# machxo2-breakout-v2.net
KiCad netlist of a schematic drawn in EAGLE
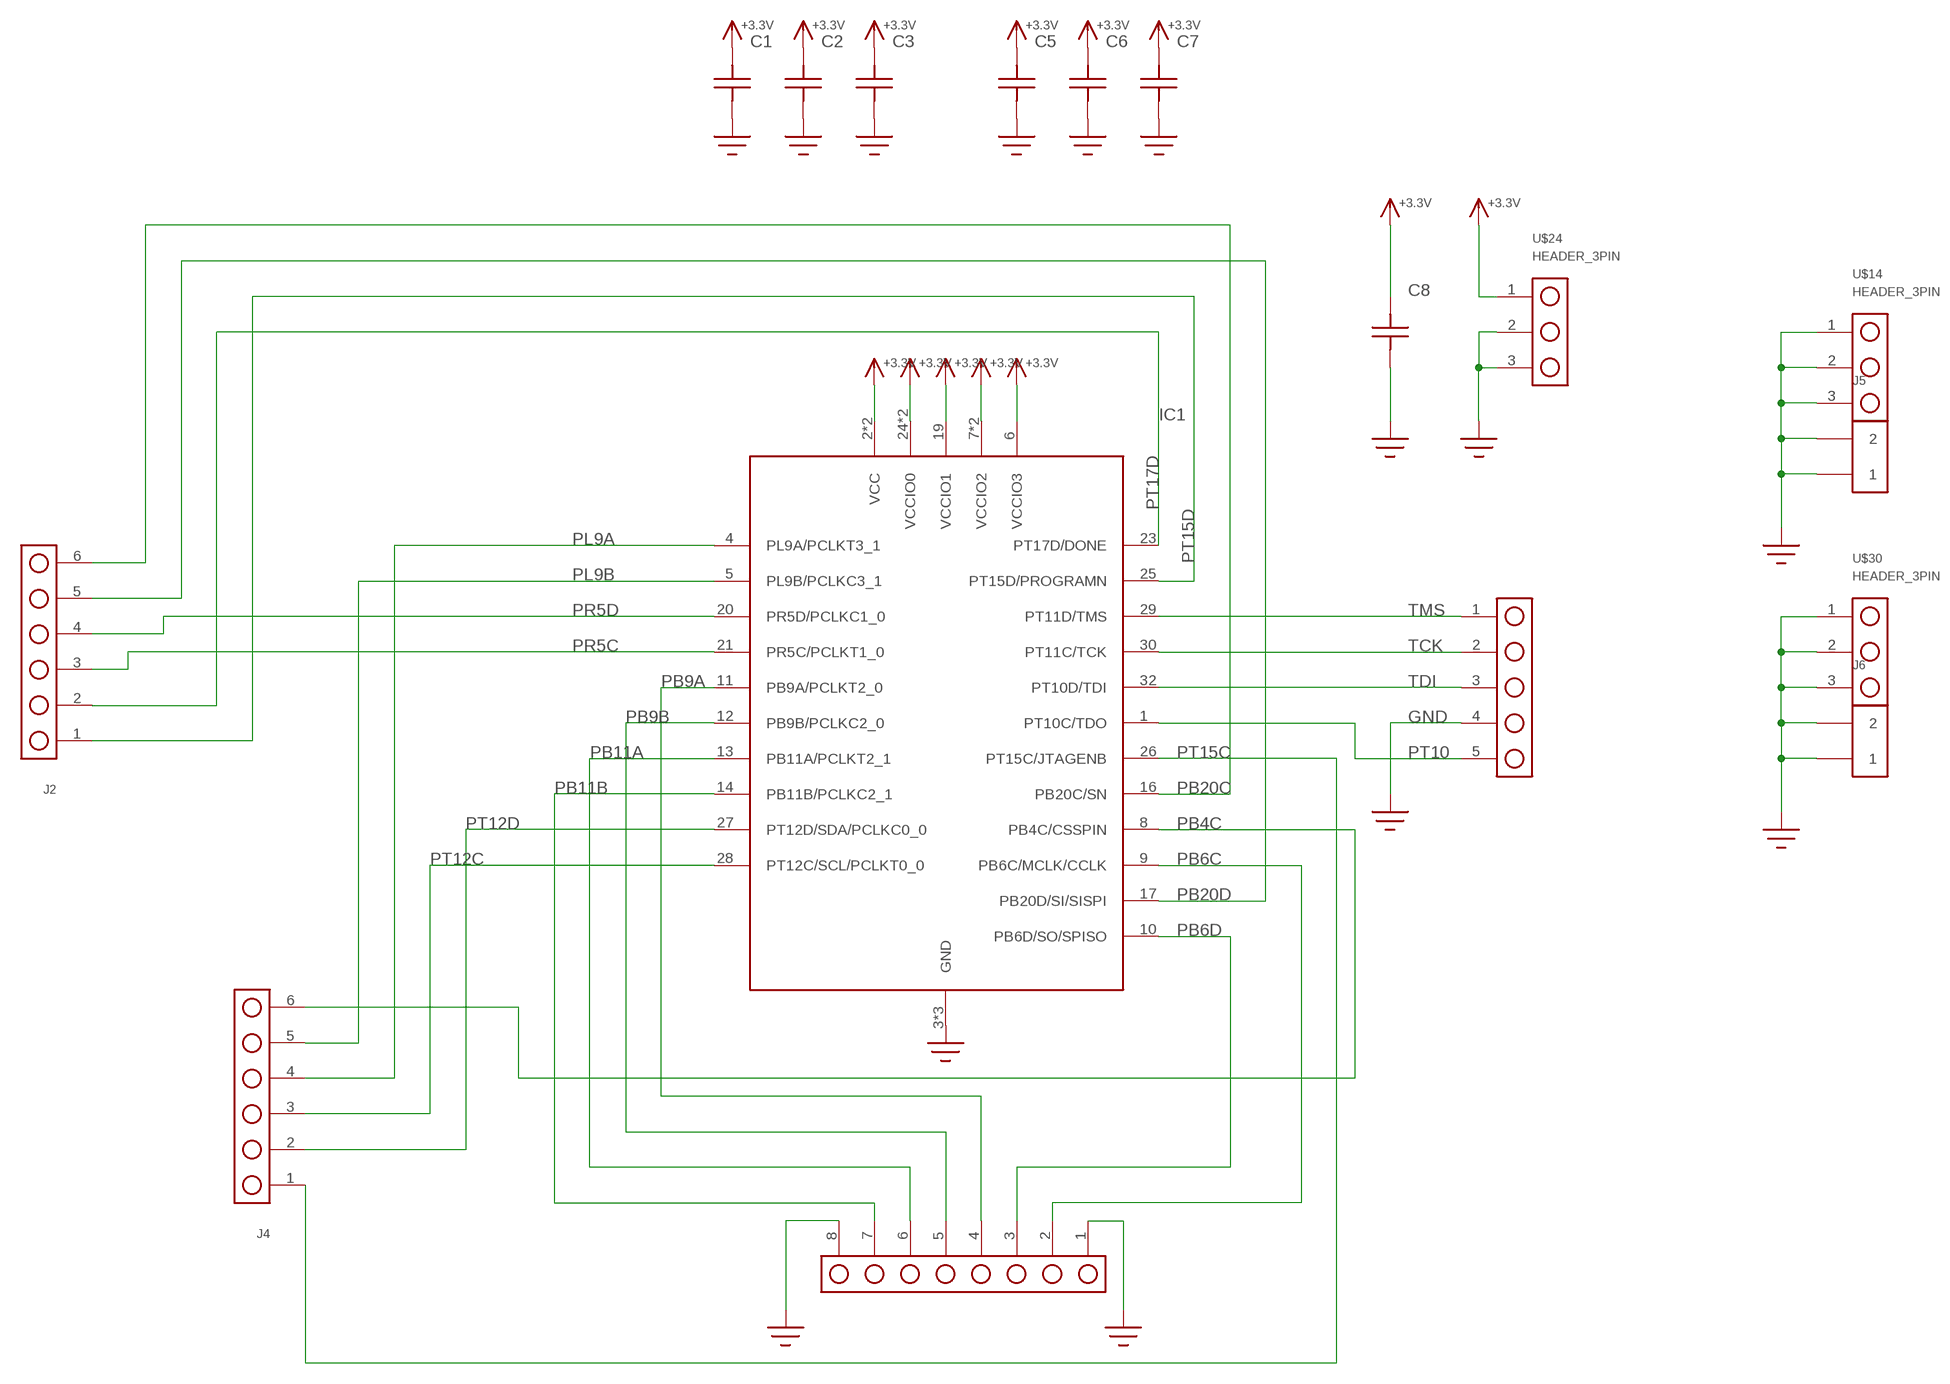
[diagram p0: schematic, sheet 1]

(export (version "E")
  (design (tool "Eeschema 10.0.6"))
  (components
    (comp (ref "C1") (value "C") (footprint "eagle-import:C0402") (libsource (lib "eagle-import") (part "C")))
    (comp (ref "C2") (value "C") (footprint "eagle-import:C0402") (libsource (lib "eagle-import") (part "C")))
    (comp (ref "C3") (value "C") (footprint "eagle-import:C0402") (libsource (lib "eagle-import") (part "C")))
    (comp (ref "C5") (value "C") (footprint "eagle-import:C0402") (libsource (lib "eagle-import") (part "C")))
    (comp (ref "C6") (value "C") (footprint "eagle-import:C0402") (libsource (lib "eagle-import") (part "C")))
    (comp (ref "C7") (value "C") (footprint "eagle-import:C0402") (libsource (lib "eagle-import") (part "C")))
    (comp (ref "C8")
      (value "C1206")
      (footprint "eagle-import:1206")
      (libsource (lib "eagle-import") (part "C1206"))
    )
    (comp (ref "IC1")
      (value "MACHXO2_1200EXTENDED")
      (footprint "eagle-import:QFN32_5X5-EXTENDED")
      (libsource (lib "eagle-import") (part "MACHXO2_1200EXTENDED"))
    )
    (comp (ref "J1")
      (value "HEADER_5PIN")
      (footprint "eagle-import:HEADER_5PIN")
      (libsource (lib "eagle-import") (part "HEADER_5PIN"))
    )
    (comp (ref "J2")
      (value "HEADER_6PIN")
      (footprint "eagle-import:HEADER_6PIN")
      (libsource (lib "eagle-import") (part "HEADER_6PIN"))
    )
    (comp (ref "J3")
      (value "HEADER_8PIN")
      (footprint "eagle-import:HEADER_8_PIN")
      (libsource (lib "eagle-import") (part "HEADER_8PIN"))
    )
    (comp (ref "J4")
      (value "HEADER_6PIN")
      (footprint "eagle-import:HEADER_6PIN")
      (libsource (lib "eagle-import") (part "HEADER_6PIN"))
    )
    (comp (ref "J5")
      (value "HEADER_2PIN")
      (footprint "eagle-import:HEADER_2PIN")
      (libsource (lib "eagle-import") (part "HEADER_2PIN"))
    )
    (comp (ref "J6")
      (value "HEADER_2PIN")
      (footprint "eagle-import:HEADER_2PIN")
      (libsource (lib "eagle-import") (part "HEADER_2PIN"))
    )
    (comp (ref "U$14")
      (value "HEADER_3PIN")
      (footprint "eagle-import:HEADER_3PIN")
      (libsource (lib "eagle-import") (part "HEADER_3PIN"))
    )
    (comp (ref "U$24")
      (value "HEADER_3PIN")
      (footprint "eagle-import:HEADER_3PIN")
      (libsource (lib "eagle-import") (part "HEADER_3PIN"))
    )
    (comp (ref "U$30")
      (value "HEADER_3PIN")
      (footprint "eagle-import:HEADER_3PIN")
      (libsource (lib "eagle-import") (part "HEADER_3PIN"))
    )
  )
  (nets
    (net (code "1") (name "+3.3V") (class "Default")
      (node (ref "C1") (pin "2") (pinfunction "P$2_2") (pintype "bidirectional"))
      (node (ref "C2") (pin "2") (pinfunction "P$2_2") (pintype "bidirectional"))
      (node (ref "C3") (pin "2") (pinfunction "P$2_2") (pintype "bidirectional"))
      (node (ref "C5") (pin "2") (pinfunction "P$2_2") (pintype "bidirectional"))
      (node (ref "C6") (pin "2") (pinfunction "P$2_2") (pintype "bidirectional"))
      (node (ref "C7") (pin "2") (pinfunction "P$2_2") (pintype "bidirectional"))
      (node (ref "C8") (pin "P$2") (pinfunction "P$2_P$2") (pintype "bidirectional"))
      (node (ref "IC1") (pin "15") (pinfunction "VCCIO2_15") (pintype "bidirectional"))
      (node (ref "IC1") (pin "18") (pinfunction "VCC_18") (pintype "bidirectional"))
      (node (ref "IC1") (pin "19") (pinfunction "VCCIO1_19") (pintype "bidirectional"))
      (node (ref "IC1") (pin "2") (pinfunction "VCC_2") (pintype "bidirectional"))
      (node (ref "IC1") (pin "24") (pinfunction "VCCIO0_24") (pintype "bidirectional"))
      (node (ref "IC1") (pin "31") (pinfunction "VCCIO0_31") (pintype "bidirectional"))
      (node (ref "IC1") (pin "6") (pinfunction "VCCIO3_6") (pintype "bidirectional"))
      (node (ref "IC1") (pin "7") (pinfunction "VCCIO2_7") (pintype "bidirectional"))
      (node (ref "U$24") (pin "1") (pinfunction "1_1") (pintype "bidirectional"))
    )
    (net (code "2") (name "/PB4C") (class "Default")
      (node (ref "IC1") (pin "8") (pinfunction "PB4C/CSSPIN_8") (pintype "bidirectional"))
      (node (ref "J4") (pin "6") (pinfunction "6_6") (pintype "bidirectional"))
    )
    (net (code "3") (name "/PB6C") (class "Default")
      (node (ref "IC1") (pin "9") (pinfunction "PB6C/MCLK/CCLK_9") (pintype "bidirectional"))
      (node (ref "J3") (pin "2") (pinfunction "2_2") (pintype "bidirectional"))
    )
    (net (code "4") (name "/PB6D") (class "Default")
      (node (ref "IC1") (pin "10") (pinfunction "PB6D/SO/SPISO_10") (pintype "bidirectional"))
      (node (ref "J3") (pin "3") (pinfunction "3_3") (pintype "bidirectional"))
    )
    (net (code "5") (name "/PB9A") (class "Default")
      (node (ref "IC1") (pin "11") (pinfunction "PB9A/PCLKT2_0_11") (pintype "bidirectional"))
      (node (ref "J3") (pin "4") (pinfunction "4_4") (pintype "bidirectional"))
    )
    (net (code "6") (name "/PB9B") (class "Default")
      (node (ref "IC1") (pin "12") (pinfunction "PB9B/PCLKC2_0_12") (pintype "bidirectional"))
      (node (ref "J3") (pin "5") (pinfunction "5_5") (pintype "bidirectional"))
    )
    (net (code "7") (name "/PB11A") (class "Default")
      (node (ref "IC1") (pin "13") (pinfunction "PB11A/PCLKT2_1_13") (pintype "bidirectional"))
      (node (ref "J3") (pin "6") (pinfunction "6_6") (pintype "bidirectional"))
    )
    (net (code "8") (name "/PB11B") (class "Default")
      (node (ref "IC1") (pin "14") (pinfunction "PB11B/PCLKC2_1_14") (pintype "bidirectional"))
      (node (ref "J3") (pin "7") (pinfunction "7_7") (pintype "bidirectional"))
    )
    (net (code "9") (name "/PB20C") (class "Default")
      (node (ref "IC1") (pin "16") (pinfunction "PB20C/SN_16") (pintype "bidirectional"))
      (node (ref "J2") (pin "6") (pinfunction "6_6") (pintype "bidirectional"))
    )
    (net (code "10") (name "/PB20D") (class "Default")
      (node (ref "IC1") (pin "17") (pinfunction "PB20D/SI/SISPI_17") (pintype "bidirectional"))
      (node (ref "J2") (pin "5") (pinfunction "5_5") (pintype "bidirectional"))
    )
    (net (code "11") (name "/PL9A") (class "Default")
      (node (ref "IC1") (pin "4") (pinfunction "PL9A/PCLKT3_1_4") (pintype "bidirectional"))
      (node (ref "J4") (pin "4") (pinfunction "4_4") (pintype "bidirectional"))
    )
    (net (code "12") (name "/PL9B") (class "Default")
      (node (ref "IC1") (pin "5") (pinfunction "PL9B/PCLKC3_1_5") (pintype "bidirectional"))
      (node (ref "J4") (pin "5") (pinfunction "5_5") (pintype "bidirectional"))
    )
    (net (code "13") (name "/PR5C") (class "Default")
      (node (ref "IC1") (pin "21") (pinfunction "PR5C/PCLKT1_0_21") (pintype "bidirectional"))
      (node (ref "J2") (pin "3") (pinfunction "3_3") (pintype "bidirectional"))
    )
    (net (code "14") (name "/PR5D") (class "Default")
      (node (ref "IC1") (pin "20") (pinfunction "PR5D/PCLKC1_0_20") (pintype "bidirectional"))
      (node (ref "J2") (pin "4") (pinfunction "4_4") (pintype "bidirectional"))
    )
    (net (code "15") (name "/PT10") (class "Default")
      (node (ref "IC1") (pin "1") (pinfunction "PT10C/TDO_1") (pintype "bidirectional"))
      (node (ref "J1") (pin "5") (pinfunction "5_5") (pintype "bidirectional"))
    )
    (net (code "16") (name "/PT12C") (class "Default")
      (node (ref "IC1") (pin "28") (pinfunction "PT12C/SCL/PCLKT0_0_28") (pintype "bidirectional"))
      (node (ref "J4") (pin "3") (pinfunction "3_3") (pintype "bidirectional"))
    )
    (net (code "17") (name "/PT12D") (class "Default")
      (node (ref "IC1") (pin "27") (pinfunction "PT12D/SDA/PCLKC0_0_27") (pintype "bidirectional"))
      (node (ref "J4") (pin "2") (pinfunction "2_2") (pintype "bidirectional"))
    )
    (net (code "18") (name "/PT15C") (class "Default")
      (node (ref "IC1") (pin "26") (pinfunction "PT15C/JTAGENB_26") (pintype "bidirectional"))
      (node (ref "J4") (pin "1") (pinfunction "1_1") (pintype "bidirectional"))
    )
    (net (code "19") (name "/PT15D") (class "Default")
      (node (ref "IC1") (pin "25") (pinfunction "PT15D/PROGRAMN_25") (pintype "bidirectional"))
      (node (ref "J2") (pin "1") (pinfunction "1_1") (pintype "bidirectional"))
    )
    (net (code "20") (name "/PT17D") (class "Default")
      (node (ref "IC1") (pin "23") (pinfunction "PT17D/DONE_23") (pintype "bidirectional"))
      (node (ref "J2") (pin "2") (pinfunction "2_2") (pintype "bidirectional"))
    )
    (net (code "21") (name "/TCK") (class "Default")
      (node (ref "IC1") (pin "30") (pinfunction "PT11C/TCK_30") (pintype "bidirectional"))
      (node (ref "J1") (pin "2") (pinfunction "2_2") (pintype "bidirectional"))
    )
    (net (code "22") (name "/TDI") (class "Default")
      (node (ref "IC1") (pin "32") (pinfunction "PT10D/TDI_32") (pintype "bidirectional"))
      (node (ref "J1") (pin "3") (pinfunction "3_3") (pintype "bidirectional"))
    )
    (net (code "23") (name "/TMS") (class "Default")
      (node (ref "IC1") (pin "29") (pinfunction "PT11D/TMS_29") (pintype "bidirectional"))
      (node (ref "J1") (pin "1") (pinfunction "1_1") (pintype "bidirectional"))
    )
    (net (code "24") (name "GND") (class "Default")
      (node (ref "C1") (pin "1") (pinfunction "P$1_1") (pintype "bidirectional"))
      (node (ref "C2") (pin "1") (pinfunction "P$1_1") (pintype "bidirectional"))
      (node (ref "C3") (pin "1") (pinfunction "P$1_1") (pintype "bidirectional"))
      (node (ref "C5") (pin "1") (pinfunction "P$1_1") (pintype "bidirectional"))
      (node (ref "C6") (pin "1") (pinfunction "P$1_1") (pintype "bidirectional"))
      (node (ref "C7") (pin "1") (pinfunction "P$1_1") (pintype "bidirectional"))
      (node (ref "C8") (pin "P$1") (pinfunction "P$1_P$1") (pintype "bidirectional"))
      (node (ref "IC1") (pin "22") (pinfunction "GND_22") (pintype "bidirectional"))
      (node (ref "IC1") (pin "3") (pinfunction "GND_3") (pintype "bidirectional"))
      (node (ref "IC1") (pin "PAD") (pinfunction "GND_PAD") (pintype "bidirectional"))
      (node (ref "J1") (pin "4") (pinfunction "4_4") (pintype "bidirectional"))
      (node (ref "J3") (pin "1") (pinfunction "1_1") (pintype "bidirectional"))
      (node (ref "J3") (pin "8") (pinfunction "8_8") (pintype "bidirectional"))
      (node (ref "J5") (pin "1") (pinfunction "1_1") (pintype "bidirectional"))
      (node (ref "J5") (pin "2") (pinfunction "2_2") (pintype "bidirectional"))
      (node (ref "J6") (pin "1") (pinfunction "1_1") (pintype "bidirectional"))
      (node (ref "J6") (pin "2") (pinfunction "2_2") (pintype "bidirectional"))
      (node (ref "U$14") (pin "1") (pinfunction "1_1") (pintype "bidirectional"))
      (node (ref "U$14") (pin "2") (pinfunction "2_2") (pintype "bidirectional"))
      (node (ref "U$14") (pin "3") (pinfunction "3_3") (pintype "bidirectional"))
      (node (ref "U$24") (pin "2") (pinfunction "2_2") (pintype "bidirectional"))
      (node (ref "U$24") (pin "3") (pinfunction "3_3") (pintype "bidirectional"))
      (node (ref "U$30") (pin "1") (pinfunction "1_1") (pintype "bidirectional"))
      (node (ref "U$30") (pin "2") (pinfunction "2_2") (pintype "bidirectional"))
      (node (ref "U$30") (pin "3") (pinfunction "3_3") (pintype "bidirectional"))
    )
  )
)
